# prototype_WLCSP.net
KiCad netlist of a schematic drawn in EAGLE
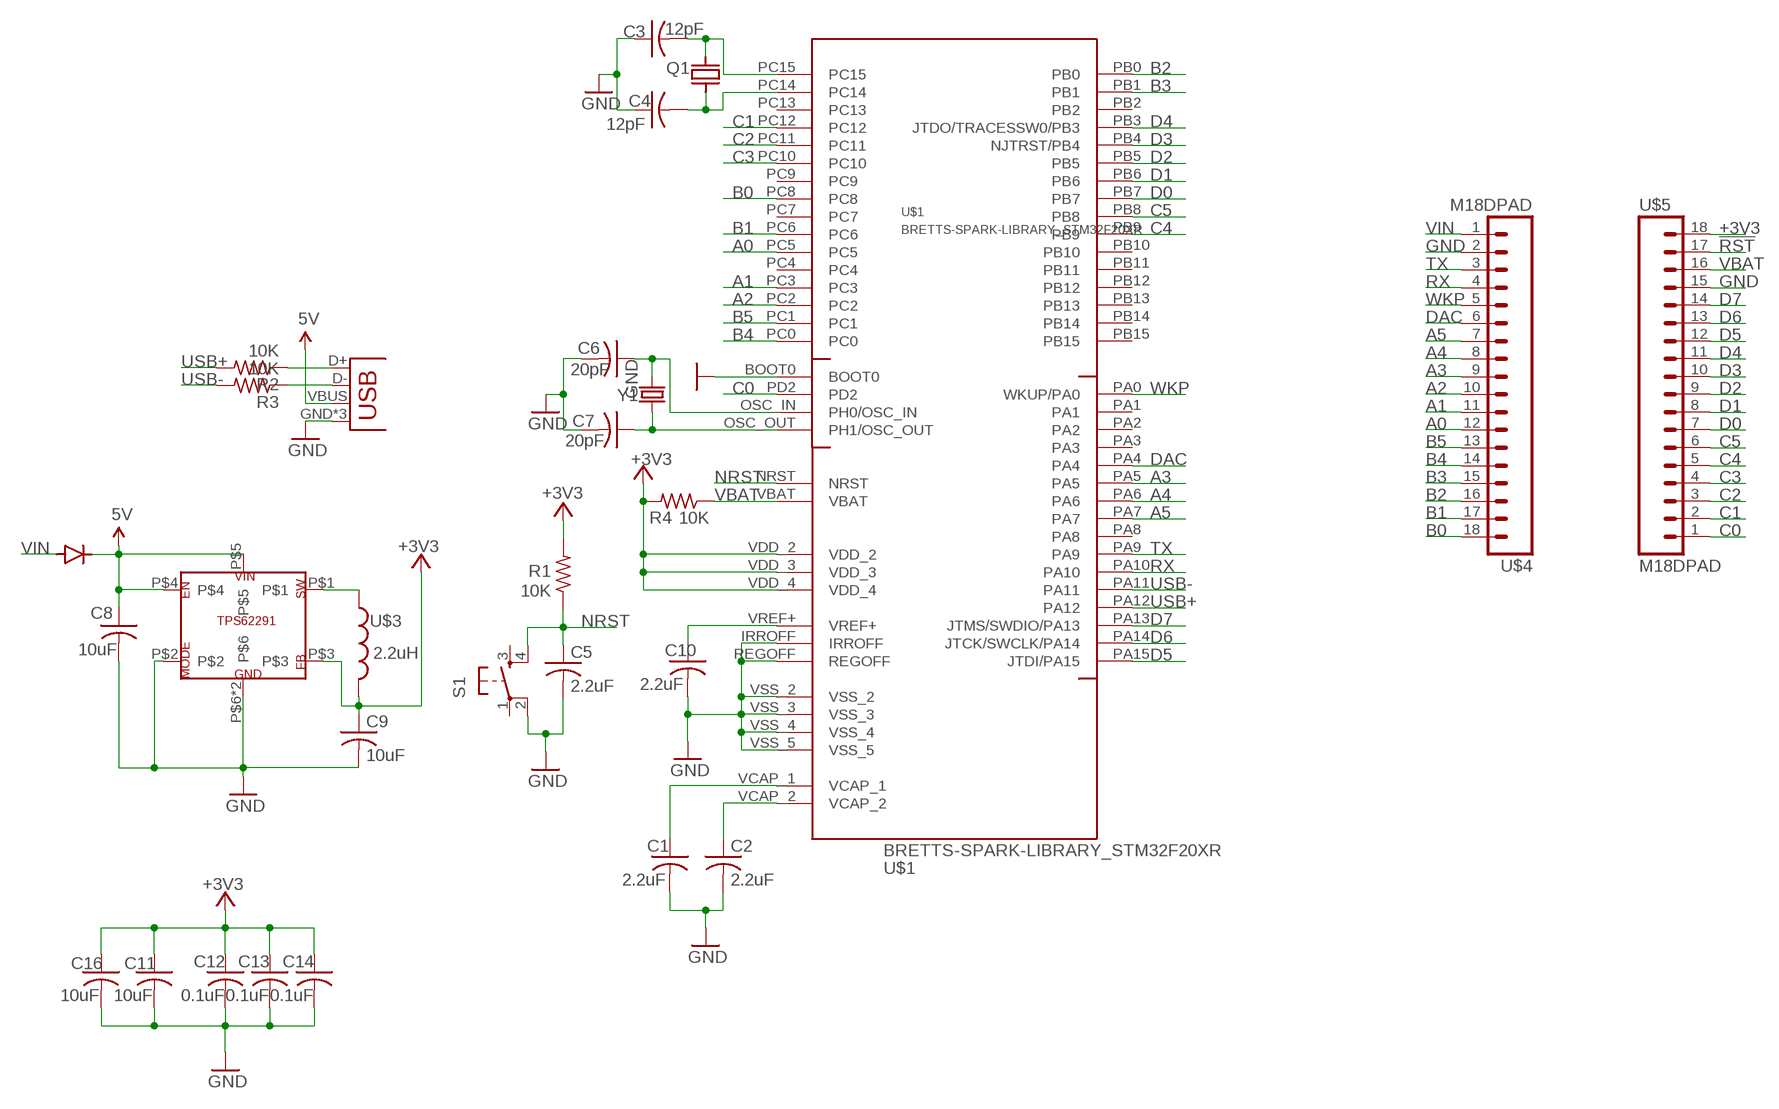
[diagram p0: schematic, sheet 1]

(export (version "E")
  (design (tool "Eeschema 10.0.6"))
  (components
    (comp (ref "C1")
      (value "2.2uF")
      (footprint "eagle-import:SPARK_C0402_B")
      (libsource (lib "eagle-import") (part "SPARK_C-US"))
    )
    (comp (ref "C2")
      (value "2.2uF")
      (footprint "eagle-import:SPARK_C0402_B")
      (libsource (lib "eagle-import") (part "SPARK_C-US"))
    )
    (comp (ref "C3")
      (value "12pF")
      (footprint "eagle-import:SPARK_C0402_B")
      (libsource (lib "eagle-import") (part "SPARK_C-US"))
    )
    (comp (ref "C4")
      (value "12pF")
      (footprint "eagle-import:SPARK_C0402_B")
      (libsource (lib "eagle-import") (part "SPARK_C-US"))
    )
    (comp (ref "C5")
      (value "2.2uF")
      (footprint "eagle-import:SPARK_C0402_B")
      (libsource (lib "eagle-import") (part "SPARK_C-US"))
    )
    (comp (ref "C6")
      (value "20pF")
      (footprint "eagle-import:SPARK_C0402_B")
      (libsource (lib "eagle-import") (part "SPARK_C-US"))
    )
    (comp (ref "C7")
      (value "20pF")
      (footprint "eagle-import:SPARK_C0402_B")
      (libsource (lib "eagle-import") (part "SPARK_C-US"))
    )
    (comp (ref "C8")
      (value "10uF")
      (footprint "eagle-import:BRETTS-SPARK-LIBRARY_C0603_B")
      (libsource (lib "eagle-import") (part "BRETTS-SPARK-LIBRARY_C-US0603"))
    )
    (comp (ref "C9")
      (value "10uF")
      (footprint "eagle-import:BRETTS-SPARK-LIBRARY_C0603_B")
      (libsource (lib "eagle-import") (part "BRETTS-SPARK-LIBRARY_C-US0603"))
    )
    (comp (ref "C10")
      (value "2.2uF")
      (footprint "eagle-import:SPARK_C0402_B")
      (libsource (lib "eagle-import") (part "SPARK_C-US"))
    )
    (comp (ref "C11")
      (value "10uF")
      (footprint "eagle-import:BRETTS-SPARK-LIBRARY_C0603_B")
      (libsource (lib "eagle-import") (part "BRETTS-SPARK-LIBRARY_C-US0603"))
    )
    (comp (ref "C12")
      (value "0.1uF")
      (footprint "eagle-import:SPARK_C0402_B")
      (libsource (lib "eagle-import") (part "SPARK_C-US"))
    )
    (comp (ref "C13")
      (value "0.1uF")
      (footprint "eagle-import:SPARK_C0402_B")
      (libsource (lib "eagle-import") (part "SPARK_C-US"))
    )
    (comp (ref "C14")
      (value "0.1uF")
      (footprint "eagle-import:SPARK_C0402_B")
      (libsource (lib "eagle-import") (part "SPARK_C-US"))
    )
    (comp (ref "C16")
      (value "10uF")
      (footprint "eagle-import:BRETTS-SPARK-LIBRARY_C0603_B")
      (libsource (lib "eagle-import") (part "BRETTS-SPARK-LIBRARY_C-US0603"))
    )
    (comp (ref "JP1")
      (value "SPARK_USB-MICROB")
      (footprint "eagle-import:SPARK_USB-MICROB")
      (libsource (lib "eagle-import") (part "SPARK_USB-MICROB"))
    )
    (comp (ref "Q1")
      (value "SPARK_Q_FC135")
      (footprint "eagle-import:SPARK_FC135")
      (libsource (lib "eagle-import") (part "SPARK_Q_FC135"))
    )
    (comp (ref "R1")
      (value "10K")
      (footprint "eagle-import:SPARK_R0402_B")
      (libsource (lib "eagle-import") (part "SPARK_R-US_"))
    )
    (comp (ref "R2")
      (value "10K")
      (footprint "eagle-import:SPARK_R0402_B")
      (libsource (lib "eagle-import") (part "SPARK_R-US_"))
    )
    (comp (ref "R3")
      (value "10K")
      (footprint "eagle-import:SPARK_R0402_B")
      (libsource (lib "eagle-import") (part "SPARK_R-US_"))
    )
    (comp (ref "R4")
      (value "10K")
      (footprint "eagle-import:SPARK_R0402_B")
      (libsource (lib "eagle-import") (part "SPARK_R-US_"))
    )
    (comp (ref "S1")
      (value "SPARK_TAC_SWITCHSMD")
      (footprint "eagle-import:SPARK_TACTILE_SWITCH_SMD")
      (libsource (lib "eagle-import") (part "SPARK_TAC_SWITCHSMD"))
    )
    (comp (ref "U$1")
      (value "BRETTS-SPARK-LIBRARY_STM32F20XR")
      (footprint "eagle-import:STM32F205_WLCSP")
      (libsource (lib "eagle-import") (part "BRETTS-SPARK-LIBRARY_STM32F20XR"))
    )
    (comp (ref "U$2")
      (value "PARTICLE_TPS62291DRV")
      (footprint "eagle-import:PARTICLE_S-PWSON-N6")
      (libsource (lib "eagle-import") (part "PARTICLE_TPS62291DRV"))
    )
    (comp (ref "U$3")
      (value "2.2uH")
      (footprint "eagle-import:PARTICLE_INDUCTOR-NR3015")
      (libsource (lib "eagle-import") (part "PARTICLE_INDUCTORB"))
    )
    (comp (ref "U$4")
      (value "M18DPAD")
      (footprint "eagle-import:PARTICLE_1X18-D-PADS")
      (libsource (lib "eagle-import") (part "PARTICLE_M18DPAD"))
    )
    (comp (ref "U$5")
      (value "M18DPAD")
      (footprint "eagle-import:PARTICLE_1X18-D-PADS")
      (libsource (lib "eagle-import") (part "PARTICLE_M18DPAD"))
    )
    (comp (ref "U$6")
      (value "PARTICLE_DIODE_NT")
      (footprint "eagle-import:PARTICLE_DIODE-DO-220AA_NT(SMP)")
      (libsource (lib "eagle-import") (part "PARTICLE_DIODE_NT"))
    )
    (comp (ref "Y1")
      (value "SPARKFUN-FREQCTRL_CRYSTAL5X3")
      (footprint "eagle-import:SPARKFUN-FREQCTRL_CRYSTAL-SMD-5X3")
      (libsource (lib "eagle-import") (part "SPARKFUN-FREQCTRL_CRYSTAL5X3"))
    )
  )
  (nets
    (net (code "1") (name "+3V3") (class "Default")
      (node (ref "C11") (pin "1") (pinfunction "1_1") (pintype "passive"))
      (node (ref "C12") (pin "1") (pinfunction "1_1") (pintype "passive"))
      (node (ref "C13") (pin "1") (pinfunction "1_1") (pintype "passive"))
      (node (ref "C14") (pin "1") (pinfunction "1_1") (pintype "passive"))
      (node (ref "C16") (pin "1") (pinfunction "1_1") (pintype "passive"))
      (node (ref "C9") (pin "1") (pinfunction "1_1") (pintype "passive"))
      (node (ref "R1") (pin "2") (pinfunction "2_2") (pintype "passive"))
      (node (ref "R4") (pin "2") (pinfunction "2_2") (pintype "passive"))
      (node (ref "U$1") (pin "VDD_2") (pinfunction "VDD_2_VDD_2") (pintype "power_in"))
      (node (ref "U$1") (pin "VDD_3") (pinfunction "VDD_3_VDD_3") (pintype "power_in"))
      (node (ref "U$1") (pin "VDD_4") (pinfunction "VDD_4_VDD_4") (pintype "power_in"))
      (node (ref "U$2") (pin "P$3") (pinfunction "P$3_P$3") (pintype "bidirectional"))
      (node (ref "U$3") (pin "2") (pinfunction "2_2") (pintype "passive"))
      (node (ref "U$5") (pin "18") (pinfunction "18_18") (pintype "passive"))
    )
    (net (code "2") (name "/A0") (class "Default")
      (node (ref "U$1") (pin "PC5") (pinfunction "PC5_PC5") (pintype "bidirectional"))
      (node (ref "U$4") (pin "12") (pinfunction "12_12") (pintype "passive"))
    )
    (net (code "3") (name "/A1") (class "Default")
      (node (ref "U$1") (pin "PC3") (pinfunction "PC3_PC3") (pintype "bidirectional"))
      (node (ref "U$4") (pin "11") (pinfunction "11_11") (pintype "passive"))
    )
    (net (code "4") (name "/A2") (class "Default")
      (node (ref "U$1") (pin "PC2") (pinfunction "PC2_PC2") (pintype "bidirectional"))
      (node (ref "U$4") (pin "10") (pinfunction "10_10") (pintype "passive"))
    )
    (net (code "5") (name "/A3") (class "Default")
      (node (ref "U$1") (pin "PA5") (pinfunction "PA5_PA5") (pintype "bidirectional"))
      (node (ref "U$4") (pin "9") (pinfunction "9_9") (pintype "passive"))
    )
    (net (code "6") (name "/A4") (class "Default")
      (node (ref "U$1") (pin "PA6") (pinfunction "PA6_PA6") (pintype "bidirectional"))
      (node (ref "U$4") (pin "8") (pinfunction "8_8") (pintype "passive"))
    )
    (net (code "7") (name "/A5") (class "Default")
      (node (ref "U$1") (pin "PA7") (pinfunction "PA7_PA7") (pintype "bidirectional"))
      (node (ref "U$4") (pin "7") (pinfunction "7_7") (pintype "passive"))
    )
    (net (code "8") (name "/B0") (class "Default")
      (node (ref "U$1") (pin "PC8") (pinfunction "PC8_PC8") (pintype "bidirectional"))
      (node (ref "U$4") (pin "18") (pinfunction "18_18") (pintype "passive"))
    )
    (net (code "9") (name "/B1") (class "Default")
      (node (ref "U$1") (pin "PC6") (pinfunction "PC6_PC6") (pintype "bidirectional"))
      (node (ref "U$4") (pin "17") (pinfunction "17_17") (pintype "passive"))
    )
    (net (code "10") (name "/B2") (class "Default")
      (node (ref "U$1") (pin "PB0") (pinfunction "PB0_PB0") (pintype "bidirectional"))
      (node (ref "U$4") (pin "16") (pinfunction "16_16") (pintype "passive"))
    )
    (net (code "11") (name "/B3") (class "Default")
      (node (ref "U$1") (pin "PB1") (pinfunction "PB1_PB1") (pintype "bidirectional"))
      (node (ref "U$4") (pin "15") (pinfunction "15_15") (pintype "passive"))
    )
    (net (code "12") (name "/B4") (class "Default")
      (node (ref "U$1") (pin "PC0") (pinfunction "PC0_PC0") (pintype "bidirectional"))
      (node (ref "U$4") (pin "14") (pinfunction "14_14") (pintype "passive"))
    )
    (net (code "13") (name "/B5") (class "Default")
      (node (ref "U$1") (pin "PC1") (pinfunction "PC1_PC1") (pintype "bidirectional"))
      (node (ref "U$4") (pin "13") (pinfunction "13_13") (pintype "passive"))
    )
    (net (code "14") (name "/C0") (class "Default")
      (node (ref "U$1") (pin "PD2") (pinfunction "PD2_PD2") (pintype "bidirectional"))
      (node (ref "U$5") (pin "1") (pinfunction "1_1") (pintype "passive"))
    )
    (net (code "15") (name "/C1") (class "Default")
      (node (ref "U$1") (pin "PC12") (pinfunction "PC12_PC12") (pintype "bidirectional"))
      (node (ref "U$5") (pin "2") (pinfunction "2_2") (pintype "passive"))
    )
    (net (code "16") (name "/C2") (class "Default")
      (node (ref "U$1") (pin "PC11") (pinfunction "PC11_PC11") (pintype "bidirectional"))
      (node (ref "U$5") (pin "3") (pinfunction "3_3") (pintype "passive"))
    )
    (net (code "17") (name "/C3") (class "Default")
      (node (ref "U$1") (pin "PC10") (pinfunction "PC10_PC10") (pintype "bidirectional"))
      (node (ref "U$5") (pin "4") (pinfunction "4_4") (pintype "passive"))
    )
    (net (code "18") (name "/C4") (class "Default")
      (node (ref "U$1") (pin "PB9") (pinfunction "PB9_PB9") (pintype "bidirectional"))
      (node (ref "U$5") (pin "5") (pinfunction "5_5") (pintype "passive"))
    )
    (net (code "19") (name "/C5") (class "Default")
      (node (ref "U$1") (pin "PB8") (pinfunction "PB8_PB8") (pintype "bidirectional"))
      (node (ref "U$5") (pin "6") (pinfunction "6_6") (pintype "passive"))
    )
    (net (code "20") (name "/D0") (class "Default")
      (node (ref "U$1") (pin "PB7") (pinfunction "PB7_PB7") (pintype "bidirectional"))
      (node (ref "U$5") (pin "7") (pinfunction "7_7") (pintype "passive"))
    )
    (net (code "21") (name "/D1") (class "Default")
      (node (ref "U$1") (pin "PB6") (pinfunction "PB6_PB6") (pintype "bidirectional"))
      (node (ref "U$5") (pin "8") (pinfunction "8_8") (pintype "passive"))
    )
    (net (code "22") (name "/D2") (class "Default")
      (node (ref "U$1") (pin "PB5") (pinfunction "PB5_PB5") (pintype "bidirectional"))
      (node (ref "U$5") (pin "9") (pinfunction "9_9") (pintype "passive"))
    )
    (net (code "23") (name "/D3") (class "Default")
      (node (ref "U$1") (pin "PB4") (pinfunction "NJTRST/PB4_PB4") (pintype "bidirectional"))
      (node (ref "U$5") (pin "10") (pinfunction "10_10") (pintype "passive"))
    )
    (net (code "24") (name "/D4") (class "Default")
      (node (ref "U$1") (pin "PB3") (pinfunction "JTDO/TRACESSW0/PB3_PB3") (pintype "bidirectional"))
      (node (ref "U$5") (pin "11") (pinfunction "11_11") (pintype "passive"))
    )
    (net (code "25") (name "/D5") (class "Default")
      (node (ref "U$1") (pin "PA15") (pinfunction "JTDI/PA15_PA15") (pintype "bidirectional"))
      (node (ref "U$5") (pin "12") (pinfunction "12_12") (pintype "passive"))
    )
    (net (code "26") (name "/D6") (class "Default")
      (node (ref "U$1") (pin "PA14") (pinfunction "JTCK/SWCLK/PA14_PA14") (pintype "bidirectional"))
      (node (ref "U$5") (pin "13") (pinfunction "13_13") (pintype "passive"))
    )
    (net (code "27") (name "/D7") (class "Default")
      (node (ref "U$1") (pin "PA13") (pinfunction "JTMS/SWDIO/PA13_PA13") (pintype "bidirectional"))
      (node (ref "U$5") (pin "14") (pinfunction "14_14") (pintype "passive"))
    )
    (net (code "28") (name "/DAC") (class "Default")
      (node (ref "U$1") (pin "PA4") (pinfunction "PA4_PA4") (pintype "bidirectional"))
      (node (ref "U$4") (pin "6") (pinfunction "6_6") (pintype "passive"))
    )
    (net (code "29") (name "/NRST") (class "Default")
      (node (ref "C5") (pin "1") (pinfunction "1_1") (pintype "passive"))
      (node (ref "R1") (pin "1") (pinfunction "1_1") (pintype "passive"))
      (node (ref "S1") (pin "4") (pinfunction "4_4") (pintype "passive"))
      (node (ref "U$1") (pin "NRST") (pinfunction "NRST_NRST") (pintype "power_in"))
    )
    (net (code "30") (name "/RX") (class "Default")
      (node (ref "U$1") (pin "PA10") (pinfunction "PA10_PA10") (pintype "bidirectional"))
      (node (ref "U$4") (pin "4") (pinfunction "4_4") (pintype "passive"))
    )
    (net (code "31") (name "/TX") (class "Default")
      (node (ref "U$1") (pin "PA9") (pinfunction "PA9_PA9") (pintype "bidirectional"))
      (node (ref "U$4") (pin "3") (pinfunction "3_3") (pintype "passive"))
    )
    (net (code "32") (name "/USB+") (class "Default")
      (node (ref "R2") (pin "2") (pinfunction "2_2") (pintype "passive"))
      (node (ref "U$1") (pin "PA12") (pinfunction "PA12_PA12") (pintype "bidirectional"))
    )
    (net (code "33") (name "/USB-") (class "Default")
      (node (ref "R3") (pin "2") (pinfunction "2_2") (pintype "passive"))
      (node (ref "U$1") (pin "PA11") (pinfunction "PA11_PA11") (pintype "bidirectional"))
    )
    (net (code "34") (name "/VBAT") (class "Default")
      (node (ref "R4") (pin "1") (pinfunction "1_1") (pintype "passive"))
      (node (ref "U$1") (pin "VBAT") (pinfunction "VBAT_VBAT") (pintype "power_in"))
      (node (ref "U$5") (pin "16") (pinfunction "16_16") (pintype "passive"))
    )
    (net (code "35") (name "/VIN") (class "Default")
      (node (ref "U$4") (pin "1") (pinfunction "1_1") (pintype "passive"))
      (node (ref "U$6") (pin "ANODE") (pinfunction "ANODE_ANODE") (pintype "bidirectional"))
    )
    (net (code "36") (name "/WKP") (class "Default")
      (node (ref "U$1") (pin "PA0") (pinfunction "WKUP/PA0_PA0") (pintype "bidirectional"))
      (node (ref "U$4") (pin "5") (pinfunction "5_5") (pintype "passive"))
    )
    (net (code "37") (name "/~{RST}") (class "Default")
      (node (ref "U$5") (pin "17") (pinfunction "17_17") (pintype "passive"))
    )
    (net (code "38") (name "5V") (class "Default")
      (node (ref "C8") (pin "1") (pinfunction "1_1") (pintype "passive"))
      (node (ref "JP1") (pin "VBUS") (pinfunction "VBUS_VBUS") (pintype "bidirectional"))
      (node (ref "U$2") (pin "P$4") (pinfunction "P$4_P$4") (pintype "bidirectional"))
      (node (ref "U$2") (pin "P$5") (pinfunction "P$5_P$5") (pintype "bidirectional"))
      (node (ref "U$6") (pin "CATHODE") (pinfunction "CATHODE_CATHODE") (pintype "bidirectional"))
    )
    (net (code "39") (name "GND") (class "Default")
      (node (ref "C1") (pin "2") (pinfunction "2_2") (pintype "passive"))
      (node (ref "C10") (pin "2") (pinfunction "2_2") (pintype "passive"))
      (node (ref "C11") (pin "2") (pinfunction "2_2") (pintype "passive"))
      (node (ref "C12") (pin "2") (pinfunction "2_2") (pintype "passive"))
      (node (ref "C13") (pin "2") (pinfunction "2_2") (pintype "passive"))
      (node (ref "C14") (pin "2") (pinfunction "2_2") (pintype "passive"))
      (node (ref "C16") (pin "2") (pinfunction "2_2") (pintype "passive"))
      (node (ref "C2") (pin "2") (pinfunction "2_2") (pintype "passive"))
      (node (ref "C3") (pin "1") (pinfunction "1_1") (pintype "passive"))
      (node (ref "C4") (pin "1") (pinfunction "1_1") (pintype "passive"))
      (node (ref "C5") (pin "2") (pinfunction "2_2") (pintype "passive"))
      (node (ref "C6") (pin "2") (pinfunction "2_2") (pintype "passive"))
      (node (ref "C7") (pin "2") (pinfunction "2_2") (pintype "passive"))
      (node (ref "C8") (pin "2") (pinfunction "2_2") (pintype "passive"))
      (node (ref "C9") (pin "2") (pinfunction "2_2") (pintype "passive"))
      (node (ref "JP1") (pin "GND") (pinfunction "GND_GND") (pintype "bidirectional"))
      (node (ref "JP1") (pin "MT1") (pinfunction "GND_MT1") (pintype "bidirectional"))
      (node (ref "JP1") (pin "MT2") (pinfunction "GND_MT2") (pintype "bidirectional"))
      (node (ref "S1") (pin "2") (pinfunction "2_2") (pintype "passive"))
      (node (ref "U$1") (pin "BOOT0") (pinfunction "BOOT0_BOOT0") (pintype "bidirectional"))
      (node (ref "U$1") (pin "IRROFF") (pinfunction "IRROFF_IRROFF") (pintype "power_in"))
      (node (ref "U$1") (pin "REGOFF") (pinfunction "REGOFF_REGOFF") (pintype "bidirectional"))
      (node (ref "U$1") (pin "VSS_2") (pinfunction "VSS_2_VSS_2") (pintype "power_in"))
      (node (ref "U$1") (pin "VSS_3") (pinfunction "VSS_3_VSS_3") (pintype "power_in"))
      (node (ref "U$1") (pin "VSS_4") (pinfunction "VSS_4_VSS_4") (pintype "power_in"))
      (node (ref "U$1") (pin "VSS_5") (pinfunction "VSS_5_VSS_5") (pintype "power_in"))
      (node (ref "U$2") (pin "P$2") (pinfunction "P$2_P$2") (pintype "bidirectional"))
      (node (ref "U$2") (pin "P$6") (pinfunction "P$6_P$6") (pintype "bidirectional"))
      (node (ref "U$2") (pin "TP") (pinfunction "P$6_TP") (pintype "bidirectional"))
      (node (ref "U$4") (pin "2") (pinfunction "2_2") (pintype "passive"))
      (node (ref "U$5") (pin "15") (pinfunction "15_15") (pintype "passive"))
    )
    (net (code "40") (name "Net-(C1-Pad1)") (class "Default")
      (node (ref "C1") (pin "1") (pinfunction "1_1") (pintype "passive"))
      (node (ref "U$1") (pin "VCAP_1") (pinfunction "VCAP_1_VCAP_1") (pintype "power_in"))
    )
    (net (code "41") (name "Net-(C2-Pad1)") (class "Default")
      (node (ref "C2") (pin "1") (pinfunction "1_1") (pintype "passive"))
      (node (ref "U$1") (pin "VCAP_2") (pinfunction "VCAP_2_VCAP_2") (pintype "power_in"))
    )
    (net (code "42") (name "Net-(C10-Pad1)") (class "Default")
      (node (ref "C10") (pin "1") (pinfunction "1_1") (pintype "passive"))
      (node (ref "U$1") (pin "VREF+") (pinfunction "VREF+_VREF+") (pintype "power_in"))
    )
    (net (code "43") (name "Net-(JP1-PadD+)") (class "Default")
      (node (ref "JP1") (pin "D+") (pinfunction "D+_D+") (pintype "bidirectional"))
      (node (ref "R2") (pin "1") (pinfunction "1_1") (pintype "passive"))
    )
    (net (code "44") (name "Net-(JP1-PadD-)") (class "Default")
      (node (ref "JP1") (pin "D-") (pinfunction "D-_D-") (pintype "bidirectional"))
      (node (ref "R3") (pin "1") (pinfunction "1_1") (pintype "passive"))
    )
    (net (code "45") (name "Net-(Q1-1)") (class "Default")
      (node (ref "C4") (pin "2") (pinfunction "2_2") (pintype "passive"))
      (node (ref "Q1") (pin "X1") (pinfunction "1_X1") (pintype "passive"))
      (node (ref "U$1") (pin "PC14") (pinfunction "PC14_PC14") (pintype "bidirectional"))
    )
    (net (code "46") (name "Net-(Q1-2)") (class "Default")
      (node (ref "C3") (pin "2") (pinfunction "2_2") (pintype "passive"))
      (node (ref "Q1") (pin "X2") (pinfunction "2_X2") (pintype "passive"))
      (node (ref "U$1") (pin "PC15") (pinfunction "PC15_PC15") (pintype "bidirectional"))
    )
    (net (code "47") (name "Net-(U$1-PH0{slash}OSC_IN)") (class "Default")
      (node (ref "C6") (pin "1") (pinfunction "1_1") (pintype "passive"))
      (node (ref "U$1") (pin "OSC_IN") (pinfunction "PH0/OSC_IN_OSC_IN") (pintype "bidirectional"))
      (node (ref "Y1") (pin "3") (pinfunction "2_3") (pintype "passive"))
    )
    (net (code "48") (name "Net-(U$1-PH1{slash}OSC_OUT)") (class "Default")
      (node (ref "C7") (pin "1") (pinfunction "1_1") (pintype "passive"))
      (node (ref "U$1") (pin "OSC_OUT") (pinfunction "PH1/OSC_OUT_OSC_OUT") (pintype "bidirectional"))
      (node (ref "Y1") (pin "1") (pinfunction "1_1") (pintype "passive"))
    )
    (net (code "49") (name "Net-(U$2-PadP$1)") (class "Default")
      (node (ref "U$2") (pin "P$1") (pinfunction "P$1_P$1") (pintype "bidirectional"))
      (node (ref "U$3") (pin "1") (pinfunction "1_1") (pintype "passive"))
    )
    (net (code "50") (name "unconnected-(S1-Pad1)") (class "Default")
      (node (ref "S1") (pin "1") (pinfunction "1_1") (pintype "passive"))
    )
    (net (code "51") (name "unconnected-(S1-Pad3)") (class "Default")
      (node (ref "S1") (pin "3") (pinfunction "3_3") (pintype "passive"))
    )
    (net (code "52") (name "unconnected-(U$1-PadPA1)") (class "Default")
      (node (ref "U$1") (pin "PA1") (pinfunction "PA1_PA1") (pintype "bidirectional"))
    )
    (net (code "53") (name "unconnected-(U$1-PadPA2)") (class "Default")
      (node (ref "U$1") (pin "PA2") (pinfunction "PA2_PA2") (pintype "bidirectional"))
    )
    (net (code "54") (name "unconnected-(U$1-PadPA3)") (class "Default")
      (node (ref "U$1") (pin "PA3") (pinfunction "PA3_PA3") (pintype "bidirectional"))
    )
    (net (code "55") (name "unconnected-(U$1-PadPA8)") (class "Default")
      (node (ref "U$1") (pin "PA8") (pinfunction "PA8_PA8") (pintype "bidirectional"))
    )
    (net (code "56") (name "unconnected-(U$1-PadPB2)") (class "Default")
      (node (ref "U$1") (pin "PB2") (pinfunction "PB2_PB2") (pintype "bidirectional"))
    )
    (net (code "57") (name "unconnected-(U$1-PadPB10)") (class "Default")
      (node (ref "U$1") (pin "PB10") (pinfunction "PB10_PB10") (pintype "bidirectional"))
    )
    (net (code "58") (name "unconnected-(U$1-PadPB11)") (class "Default")
      (node (ref "U$1") (pin "PB11") (pinfunction "PB11_PB11") (pintype "bidirectional"))
    )
    (net (code "59") (name "unconnected-(U$1-PadPB12)") (class "Default")
      (node (ref "U$1") (pin "PB12") (pinfunction "PB12_PB12") (pintype "bidirectional"))
    )
    (net (code "60") (name "unconnected-(U$1-PadPB13)") (class "Default")
      (node (ref "U$1") (pin "PB13") (pinfunction "PB13_PB13") (pintype "bidirectional"))
    )
    (net (code "61") (name "unconnected-(U$1-PadPB14)") (class "Default")
      (node (ref "U$1") (pin "PB14") (pinfunction "PB14_PB14") (pintype "bidirectional"))
    )
    (net (code "62") (name "unconnected-(U$1-PadPB15)") (class "Default")
      (node (ref "U$1") (pin "PB15") (pinfunction "PB15_PB15") (pintype "bidirectional"))
    )
    (net (code "63") (name "unconnected-(U$1-PadPC4)") (class "Default")
      (node (ref "U$1") (pin "PC4") (pinfunction "PC4_PC4") (pintype "bidirectional"))
    )
    (net (code "64") (name "unconnected-(U$1-PadPC7)") (class "Default")
      (node (ref "U$1") (pin "PC7") (pinfunction "PC7_PC7") (pintype "bidirectional"))
    )
    (net (code "65") (name "unconnected-(U$1-PadPC9)") (class "Default")
      (node (ref "U$1") (pin "PC9") (pinfunction "PC9_PC9") (pintype "bidirectional"))
    )
    (net (code "66") (name "unconnected-(U$1-PadPC13)") (class "Default")
      (node (ref "U$1") (pin "PC13") (pinfunction "PC13_PC13") (pintype "bidirectional"))
    )
  )
)
